# SIM7600G-H_USB.net
KiCad netlist of a schematic drawn in Altium Designer
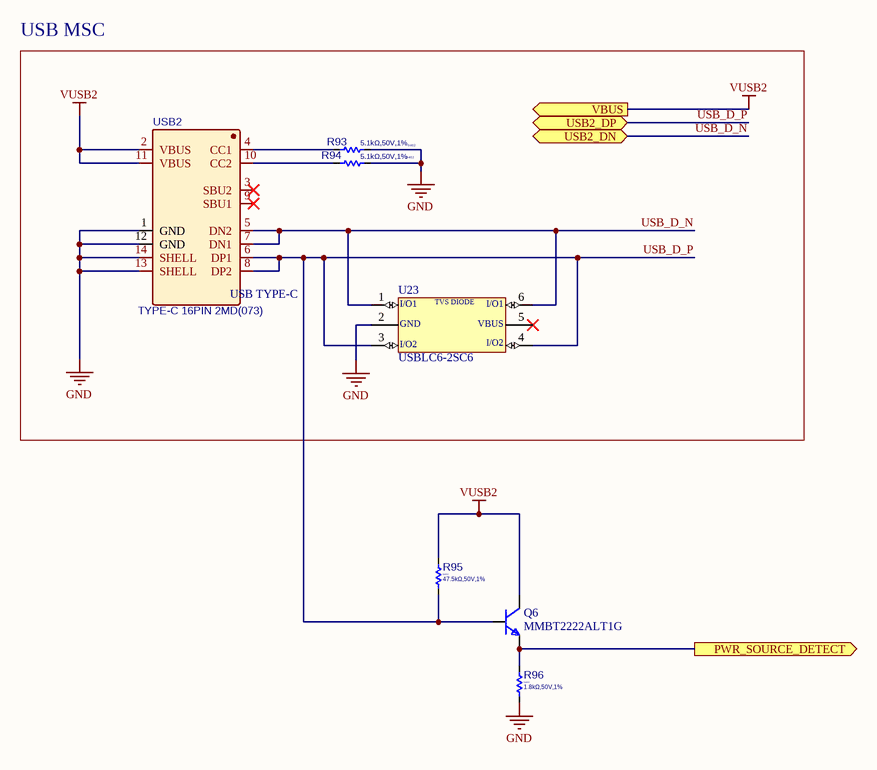
[diagram p0: SIM7600G-H_USB.SchDoc]

(export (version "E")
  (design (tool "Eeschema 10.0.6"))
  (components
    (comp (ref "Q6")
      (value "MMBT2222ALT1G")
      (footprint "SOT-23")
      (description "Bipolar (BJT) Transistor NPN 40 V 600 mA 300MHz 225 mW Surface Mount SOT-23-3 (TO-236)")
      (fields (field (name "MANUFACTURER") "ON Semiconductor"))
      (libsource (lib "MOS_TRAN") (part "MMBT2222ALT1G"))
    )
    (comp (ref "R93")
      (value "5.1kΩ,50V,1%")
      (footprint "R0402")
      (description "100mW Thick Film Resistors 75V ±100ppm/℃ ±1% 100kΩ 0603 Chip Resistor - Surface Mount ROHS")
      (fields
        (field (name "MPN") "RC0402FR-075K1L")
        (field (name "MANUFACTURER") "YAGEO")
        (field (name "PACKAGE") "0402")
      )
      (libsource (lib "RCL") (part "RC0402FR-075K1L"))
    )
    (comp (ref "R94")
      (value "5.1kΩ,50V,1%")
      (footprint "R0402")
      (description "100mW Thick Film Resistors 75V ±100ppm/℃ ±1% 100kΩ 0603 Chip Resistor - Surface Mount ROHS")
      (fields
        (field (name "MPN") "RC0402FR-075K1L")
        (field (name "MANUFACTURER") "YAGEO")
        (field (name "PACKAGE") "0402")
      )
      (libsource (lib "RCL") (part "RC0402FR-075K1L"))
    )
    (comp (ref "R95")
      (value "47.5kΩ,50V,1%")
      (footprint "R0402")
      (description "62.5mW Thick Film Resistors 50V ±100ppm/℃ ±1% 47.5kΩ 0402 Chip Resistor - Surface Mount ROHS")
      (fields
        (field (name "MANUFACTURER") "YAGEO(国巨)")
        (field (name "MPN") "AC0402FR-0747K5L")
        (field (name "PACKAGE") "0402")
      )
      (libsource (lib "RCL") (part "AC0402FR-0747K5L"))
    )
    (comp (ref "R96")
      (value "1.8kΩ,50V,1%")
      (footprint "R0402")
      (description "62.5mW Thick Film Resistors 50V ±100ppm/℃ ±1% 1.8kΩ 0402 Chip Resistor - Surface Mount ROHS")
      (fields
        (field (name "MANUFACTURER") "YAGEO")
        (field (name "MPN") "0402WGF1801TCE")
        (field (name "PACKAGE") "0402")
      )
      (libsource (lib "RCL") (part "0402WGF1801TCE"))
    )
    (comp (ref "U23")
      (value "USBLC6-2SC6")
      (footprint "SOT95P280X145-6N")
      (description "17V Clamp 5A (8/20Âµs) Ipp Tvs Diode Surface Mount SOT-23-6")
      (fields (field (name "MF") "STMicroelectronics"))
      (libsource (lib "IC") (part "USBLC6-2SC6"))
    )
    (comp (ref "USB2")
      (value "TYPE-C 16PIN 2MD(073)")
      (footprint "TYPE-C 16PIN 2MD(073)")
      (description "5A 1 Surface Mount 16P Female -25℃~+85℃ Type-C SMD USB Connectors ROHS")
      (fields (field (name "MANUFACTURER") "SHOU HAN(首韩)"))
      (libsource (lib "connector_button") (part "TYPE-C 16PIN 2MD(073)"))
    )
  )
  (nets
    (net (code "1") (name "/PWR_SOURCE_DETECT") (class "Default")
      (node (ref "Q6") (pin "2") (pinfunction "2_2") (pintype "passive"))
      (node (ref "R96") (pin "2") (pinfunction "2_2") (pintype "passive"))
    )
    (net (code "2") (name "/USB_D_N") (class "Default")
      (node (ref "U23") (pin "1") (pinfunction "I/O1_IN_1") (pintype "bidirectional"))
      (node (ref "U23") (pin "6") (pinfunction "I/O1_OUT_6") (pintype "bidirectional"))
      (node (ref "USB2") (pin "5") (pinfunction "DN2_5") (pintype "passive"))
      (node (ref "USB2") (pin "7") (pinfunction "DN1_7") (pintype "passive"))
    )
    (net (code "3") (name "/USB_D_P") (class "Default")
      (node (ref "Q6") (pin "1") (pinfunction "1_1") (pintype "passive"))
      (node (ref "R95") (pin "1") (pinfunction "1_1") (pintype "passive"))
      (node (ref "U23") (pin "3") (pinfunction "I/O2_IN_3") (pintype "bidirectional"))
      (node (ref "U23") (pin "4") (pinfunction "I/O2_OUT_4") (pintype "bidirectional"))
      (node (ref "USB2") (pin "6") (pinfunction "DP1_6") (pintype "passive"))
      (node (ref "USB2") (pin "8") (pinfunction "DP2_8") (pintype "passive"))
    )
    (net (code "4") (name "GND") (class "Default")
      (node (ref "R93") (pin "2") (pinfunction "2_2") (pintype "passive"))
      (node (ref "R94") (pin "2") (pinfunction "2_2") (pintype "passive"))
      (node (ref "R96") (pin "1") (pinfunction "1_1") (pintype "passive"))
      (node (ref "U23") (pin "2") (pinfunction "GND_2") (pintype "power_in"))
      (node (ref "USB2") (pin "1") (pinfunction "GND_1") (pintype "passive"))
      (node (ref "USB2") (pin "12") (pinfunction "GND_12") (pintype "passive"))
      (node (ref "USB2") (pin "13") (pinfunction "SHELL_13") (pintype "passive"))
      (node (ref "USB2") (pin "14") (pinfunction "SHELL_14") (pintype "passive"))
    )
    (net (code "5") (name "Net-(USB2-CC1)") (class "Default")
      (node (ref "R93") (pin "1") (pinfunction "1_1") (pintype "passive"))
      (node (ref "USB2") (pin "4") (pinfunction "CC1_4") (pintype "passive"))
    )
    (net (code "6") (name "Net-(USB2-CC2)") (class "Default")
      (node (ref "R94") (pin "1") (pinfunction "1_1") (pintype "passive"))
      (node (ref "USB2") (pin "10") (pinfunction "CC2_10") (pintype "passive"))
    )
    (net (code "7") (name "VUSB2") (class "Default")
      (node (ref "Q6") (pin "3") (pinfunction "3_3") (pintype "passive"))
      (node (ref "R95") (pin "2") (pinfunction "2_2") (pintype "passive"))
      (node (ref "USB2") (pin "11") (pinfunction "VBUS_11") (pintype "passive"))
      (node (ref "USB2") (pin "2") (pinfunction "VBUS_2") (pintype "passive"))
    )
    (net (code "8") (name "unconnected-(U23-VBUS-Pad5)") (class "Default")
      (node (ref "U23") (pin "5") (pinfunction "VBUS_5") (pintype "power_in+no_connect"))
    )
    (net (code "9") (name "unconnected-(USB2-SBU1-Pad9)") (class "Default")
      (node (ref "USB2") (pin "9") (pinfunction "SBU1_9") (pintype "passive+no_connect"))
    )
    (net (code "10") (name "unconnected-(USB2-SBU2-Pad3)") (class "Default")
      (node (ref "USB2") (pin "3") (pinfunction "SBU2_3") (pintype "passive+no_connect"))
    )
  )
)
